# Power.net
KiCad netlist of a schematic drawn in Altium Designer
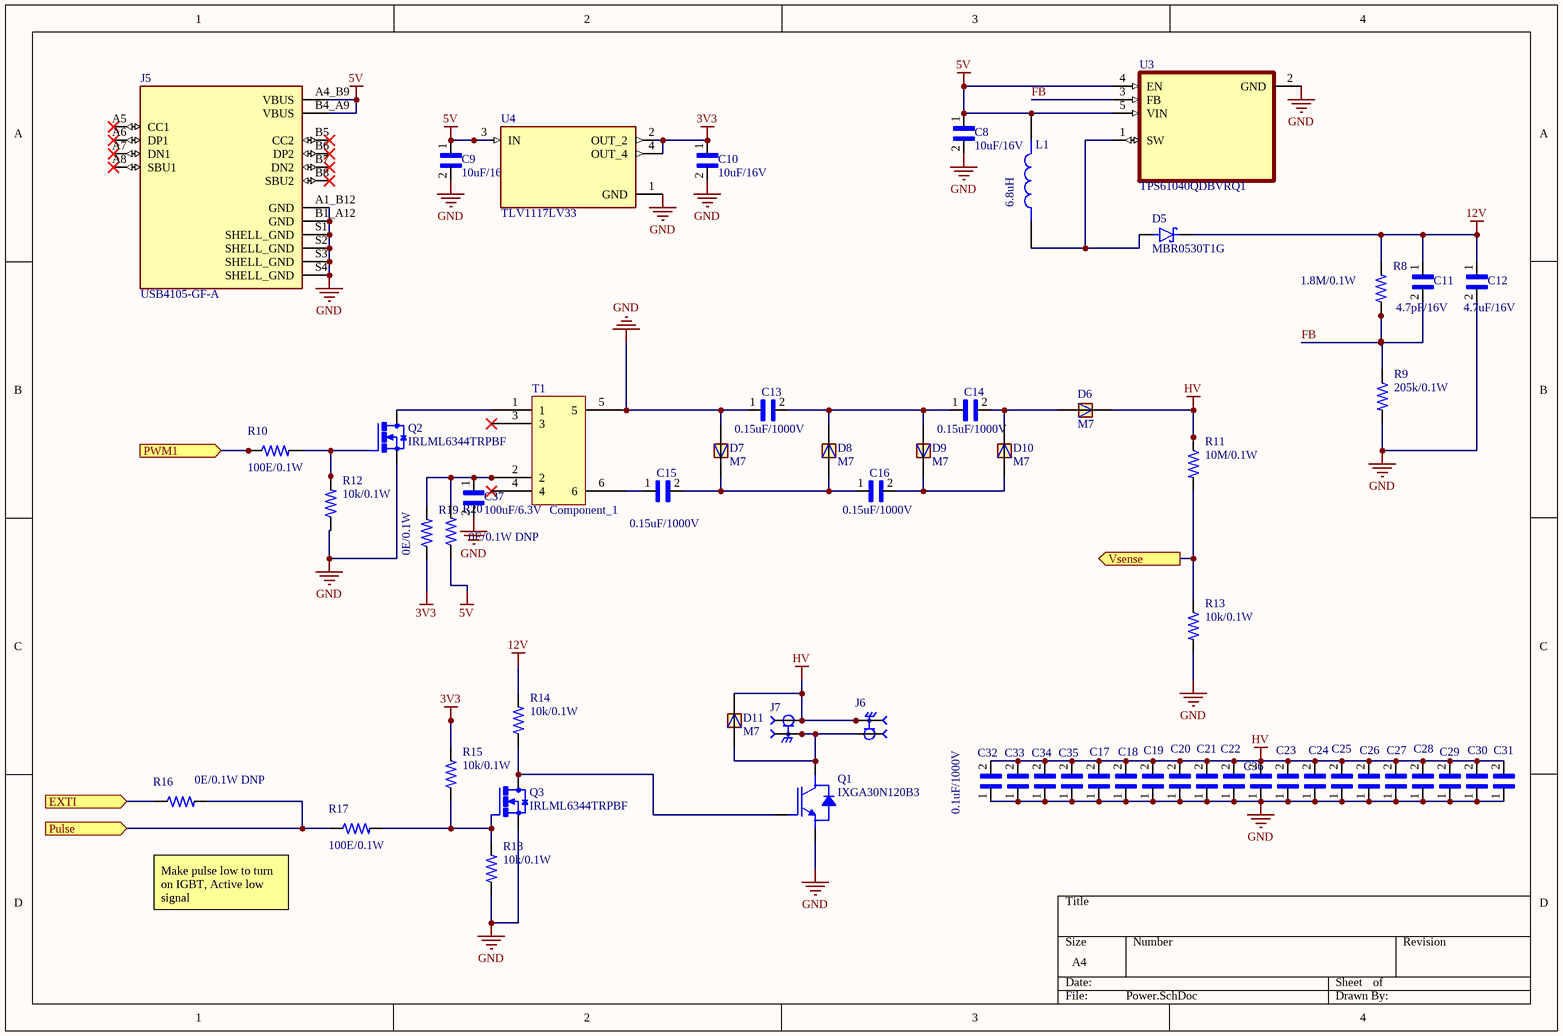
[diagram p0: Power.SchDoc]

(export (version "E")
  (design (tool "Eeschema 10.0.6"))
  (components
    (comp (ref "C8")
      (value "10uF/16V")
      (footprint "CAPC1608X90")
      (description "CAP CER 10UF 16V X5R 0603")
      (fields (field (name "MP") "CC0603MRX5R7BB106"))
      (libsource (lib "Capacitor_0603") (part "CC0603MRX5R7BB106"))
    )
    (comp (ref "C9")
      (value "10uF/16V")
      (footprint "CAPC1608X90")
      (description "CAP CER 10UF 16V X5R 0603")
      (fields (field (name "MP") "CC0603MRX5R7BB106"))
      (libsource (lib "Capacitor_0603") (part "CC0603MRX5R7BB106"))
    )
    (comp (ref "C10")
      (value "10uF/16V")
      (footprint "CAPC1608X90")
      (description "CAP CER 10UF 16V X5R 0603")
      (fields (field (name "MP") "CC0603MRX5R7BB106"))
      (libsource (lib "Capacitor_0603") (part "CC0603MRX5R7BB106"))
    )
    (comp (ref "C11")
      (value "4.7pF/16V")
      (footprint "CAPC1608X90")
      (description "CAP CER 10UF 16V X5R 0603")
      (fields (field (name "MP") "CC0603MRX5R7BB106"))
      (libsource (lib "Capacitor_0603") (part "CC0603MRX5R7BB106"))
    )
    (comp (ref "C12")
      (value "4.7uF/16V")
      (footprint "CAPC1608X90")
      (description "CAP CER 10UF 16V X5R 0603")
      (fields (field (name "MP") "CC0603MRX5R7BB106"))
      (libsource (lib "Capacitor_0603") (part "CC0603MRX5R7BB106"))
    )
    (comp (ref "C13")
      (value "0.15uF/1000V")
      (footprint "CAPC5563X218N")
      (fields (field (name "MP") "VJ2225Y104KBGAT4X"))
      (libsource (lib "Capacitor_2225") (part "VJ2225Y104KBGAT4X"))
    )
    (comp (ref "C14")
      (value "0.15uF/1000V")
      (footprint "CAPC5563X218N")
      (fields (field (name "MP") "VJ2225Y104KBGAT4X"))
      (libsource (lib "Capacitor_2225") (part "VJ2225Y104KBGAT4X"))
    )
    (comp (ref "C15")
      (value "0.15uF/1000V")
      (footprint "CAPC5563X218N")
      (fields (field (name "MP") "VJ2225Y104KBGAT4X"))
      (libsource (lib "Capacitor_2225") (part "VJ2225Y104KBGAT4X"))
    )
    (comp (ref "C16")
      (value "0.15uF/1000V")
      (footprint "CAPC5563X218N")
      (fields (field (name "MP") "VJ2225Y104KBGAT4X"))
      (libsource (lib "Capacitor_2225") (part "VJ2225Y104KBGAT4X"))
    )
    (comp (ref "C17")
      (value "0.1uF/1000V")
      (footprint "CAPC4632X221N")
      (description "1812")
      (fields (field (name "MP") "1812CC104KAZ1A") (field (name "MF") "AVX"))
      (libsource (lib "Cap_1812") (part "1812CC104KAZ1A"))
    )
    (comp (ref "C18")
      (value "0.1uF/1000V")
      (footprint "CAPC4632X221N")
      (description "1812")
      (fields (field (name "MP") "1812CC104KAZ1A") (field (name "MF") "AVX"))
      (libsource (lib "Cap_1812") (part "1812CC104KAZ1A"))
    )
    (comp (ref "C19")
      (value "0.1uF/1000V")
      (footprint "CAPC4632X221N")
      (description "1812")
      (fields (field (name "MP") "1812CC104KAZ1A") (field (name "MF") "AVX"))
      (libsource (lib "Cap_1812") (part "1812CC104KAZ1A"))
    )
    (comp (ref "C20")
      (value "0.1uF/1000V")
      (footprint "CAPC4632X221N")
      (description "1812")
      (fields (field (name "MP") "1812CC104KAZ1A") (field (name "MF") "AVX"))
      (libsource (lib "Cap_1812") (part "1812CC104KAZ1A"))
    )
    (comp (ref "C21")
      (value "0.1uF/1000V")
      (footprint "CAPC4632X221N")
      (description "1812")
      (fields (field (name "MP") "1812CC104KAZ1A") (field (name "MF") "AVX"))
      (libsource (lib "Cap_1812") (part "1812CC104KAZ1A"))
    )
    (comp (ref "C22")
      (value "0.1uF/1000V")
      (footprint "CAPC4632X221N")
      (description "1812")
      (fields (field (name "MP") "1812CC104KAZ1A") (field (name "MF") "AVX"))
      (libsource (lib "Cap_1812") (part "1812CC104KAZ1A"))
    )
    (comp (ref "C23")
      (value "0.1uF/1000V")
      (footprint "CAPC4632X221N")
      (description "1812")
      (fields (field (name "MP") "1812CC104KAZ1A") (field (name "MF") "AVX"))
      (libsource (lib "Cap_1812") (part "1812CC104KAZ1A"))
    )
    (comp (ref "C24")
      (value "0.1uF/1000V")
      (footprint "CAPC4632X221N")
      (description "1812")
      (fields (field (name "MP") "1812CC104KAZ1A") (field (name "MF") "AVX"))
      (libsource (lib "Cap_1812") (part "1812CC104KAZ1A"))
    )
    (comp (ref "C25")
      (value "0.1uF/1000V")
      (footprint "CAPC4632X221N")
      (description "1812")
      (fields (field (name "MP") "1812CC104KAZ1A") (field (name "MF") "AVX"))
      (libsource (lib "Cap_1812") (part "1812CC104KAZ1A"))
    )
    (comp (ref "C26")
      (value "0.1uF/1000V")
      (footprint "CAPC4632X221N")
      (description "1812")
      (fields (field (name "MP") "1812CC104KAZ1A") (field (name "MF") "AVX"))
      (libsource (lib "Cap_1812") (part "1812CC104KAZ1A"))
    )
    (comp (ref "C27")
      (value "0.1uF/1000V")
      (footprint "CAPC4632X221N")
      (description "1812")
      (fields (field (name "MP") "1812CC104KAZ1A") (field (name "MF") "AVX"))
      (libsource (lib "Cap_1812") (part "1812CC104KAZ1A"))
    )
    (comp (ref "C28")
      (value "0.1uF/1000V")
      (footprint "CAPC4632X221N")
      (description "1812")
      (fields (field (name "MP") "1812CC104KAZ1A") (field (name "MF") "AVX"))
      (libsource (lib "Cap_1812") (part "1812CC104KAZ1A"))
    )
    (comp (ref "C29")
      (value "0.1uF/1000V")
      (footprint "CAPC4632X221N")
      (description "1812")
      (fields (field (name "MP") "1812CC104KAZ1A") (field (name "MF") "AVX"))
      (libsource (lib "Cap_1812") (part "1812CC104KAZ1A"))
    )
    (comp (ref "C30")
      (value "0.1uF/1000V")
      (footprint "CAPC4632X221N")
      (description "1812")
      (fields (field (name "MP") "1812CC104KAZ1A") (field (name "MF") "AVX"))
      (libsource (lib "Cap_1812") (part "1812CC104KAZ1A"))
    )
    (comp (ref "C31")
      (value "0.1uF/1000V")
      (footprint "CAPC4632X221N")
      (description "1812")
      (fields (field (name "MP") "1812CC104KAZ1A") (field (name "MF") "AVX"))
      (libsource (lib "Cap_1812") (part "1812CC104KAZ1A"))
    )
    (comp (ref "C32")
      (value "0.1uF/1000V")
      (footprint "CAPC4632X221N")
      (description "1812")
      (fields (field (name "MP") "1812CC104KAZ1A") (field (name "MF") "AVX"))
      (libsource (lib "Cap_1812") (part "1812CC104KAZ1A"))
    )
    (comp (ref "C33")
      (value "0.1uF/1000V")
      (footprint "CAPC4632X221N")
      (description "1812")
      (fields (field (name "MP") "1812CC104KAZ1A") (field (name "MF") "AVX"))
      (libsource (lib "Cap_1812") (part "1812CC104KAZ1A"))
    )
    (comp (ref "C34")
      (value "0.1uF/1000V")
      (footprint "CAPC4632X221N")
      (description "1812")
      (fields (field (name "MP") "1812CC104KAZ1A") (field (name "MF") "AVX"))
      (libsource (lib "Cap_1812") (part "1812CC104KAZ1A"))
    )
    (comp (ref "C35")
      (value "0.1uF/1000V")
      (footprint "CAPC4632X221N")
      (description "1812")
      (fields (field (name "MP") "1812CC104KAZ1A") (field (name "MF") "AVX"))
      (libsource (lib "Cap_1812") (part "1812CC104KAZ1A"))
    )
    (comp (ref "C36")
      (value "0.1uF/1000V")
      (footprint "CAPC4632X221N")
      (description "1812")
      (fields (field (name "MP") "1812CC104KAZ1A") (field (name "MF") "AVX"))
      (libsource (lib "Cap_1812") (part "1812CC104KAZ1A"))
    )
    (comp (ref "C37")
      (value "100uF/6.3V")
      (footprint "CAPC1608X90")
      (description "CAP CER 10UF 16V X5R 0603")
      (fields (field (name "MP") "CC0603MRX5R7BB106"))
      (libsource (lib "Capacitor_0603") (part "CC0603MRX5R7BB106"))
    )
    (comp (ref "D5")
      (value "MBR0530T1G")
      (footprint "SOD3715X145N")
      (description "SOD-123")
      (fields (field (name "MP") "BAT46W-7-F") (field (name "MF") "Diodes Inc."))
      (libsource (lib "Diode_SOD-123") (part "BAT46W-7-F"))
    )
    (comp (ref "D6")
      (value "M7")
      (footprint "DIOM505270X240")
      (description "Diode Standard 1000 V 1A Surface Mount DO-214AC (SMA)")
      (fields (field (name "MF") "Diotec Semiconductor"))
      (libsource (lib "") (part "M7_2"))
    )
    (comp (ref "D7")
      (value "M7")
      (footprint "DIOM505270X240")
      (description "Diode Standard 1000 V 1A Surface Mount DO-214AC (SMA)")
      (fields (field (name "MF") "Diotec Semiconductor"))
      (libsource (lib "") (part "M7_1"))
    )
    (comp (ref "D8")
      (value "M7")
      (footprint "DIOM505270X240")
      (description "Diode Standard 1000 V 1A Surface Mount DO-214AC (SMA)")
      (fields (field (name "MF") "Diotec Semiconductor"))
      (libsource (lib "Diode_DO-214AC-2") (part "M7"))
    )
    (comp (ref "D9")
      (value "M7")
      (footprint "DIOM505270X240")
      (description "Diode Standard 1000 V 1A Surface Mount DO-214AC (SMA)")
      (fields (field (name "MF") "Diotec Semiconductor"))
      (libsource (lib "") (part "M7_1"))
    )
    (comp (ref "D10")
      (value "M7")
      (footprint "DIOM505270X240")
      (description "Diode Standard 1000 V 1A Surface Mount DO-214AC (SMA)")
      (fields (field (name "MF") "Diotec Semiconductor"))
      (libsource (lib "Diode_DO-214AC-2") (part "M7"))
    )
    (comp (ref "D11")
      (value "M7")
      (footprint "DIOM505270X240")
      (description "Diode Standard 1000 V 1A Surface Mount DO-214AC (SMA)")
      (fields (field (name "MF") "Diotec Semiconductor"))
      (libsource (lib "Diode_DO-214AC-2") (part "M7"))
    )
    (comp (ref "J5")
      (value "USB4105-GF-A")
      (footprint "GCT_USB4105-GF-A")
      (fields (field (name "MF") "GCT"))
      (libsource (lib "USB4105-GF-A") (part "USB4105-GF-A"))
    )
    (comp (ref "J6")
      (value "SMA-J-P-X-ST-EM3")
      (footprint "SAMTEC_SMA-J-P-X-ST-EM3")
      (description "RF Connectors / Coaxial Connectors")
      (fields (field (name "MF") "Samtec"))
      (libsource (lib "SMA-J-P-X-ST-EM3") (part "SMA-J-P-X-ST-EM3"))
    )
    (comp (ref "J7")
      (value "SMA-J-P-X-ST-EM3")
      (footprint "SAMTEC_SMA-J-P-X-ST-EM3")
      (description "RF Connectors / Coaxial Connectors")
      (fields (field (name "MF") "Samtec"))
      (libsource (lib "SMA-J-P-X-ST-EM3") (part "SMA-J-P-X-ST-EM3"))
    )
    (comp (ref "L1")
      (value "6.8uH")
      (footprint "INDM3225X240N")
      (description "1210")
      (fields (field (name "DIGI-KEY_PART_NUMBER") "445-16406-2-ND") (field (name "MP") "NLCV32T-6R8M-EFR"))
      (libsource (lib "Inductor_1210") (part "NLCV32T-6R8M-EFR"))
    )
    (comp (ref "Q1")
      (value "IXGA30N120B3")
      (footprint "TO254P1524X483-3N")
      (description "TO-263-3")
      (fields (field (name "MP") "ISL9V5045S3ST"))
      (libsource (lib "IGBT_TO-263-3") (part "ISL9V5045S3ST"))
    )
    (comp (ref "Q2")
      (value "IRLML6344TRPBF")
      (footprint "SOT23")
      (description "SOT-23-3")
      (fields (field (name "MP") "MMBF170") (field (name "MF") "ON Semiconductor"))
      (libsource (lib "NMOS_SOT-23-3") (part "MMBF170"))
    )
    (comp (ref "Q3")
      (value "IRLML6344TRPBF")
      (footprint "SOT23")
      (description "SOT-23-3")
      (fields (field (name "MP") "MMBF170") (field (name "MF") "ON Semiconductor"))
      (libsource (lib "NMOS_SOT-23-3") (part "MMBF170"))
    )
    (comp (ref "R8")
      (value "1.8M/0.1W")
      (footprint "RESC1608X50N")
      (description "RES 0.27 OHM 1% 1/10W 0603")
      (fields (field (name "MF") "TE Connectivity") (field (name "TOLERANCE") "1%"))
      (libsource (lib "Resistor_0603") (part "3-1879460-5"))
    )
    (comp (ref "R9")
      (value "205k/0.1W")
      (footprint "RESC1608X50N")
      (description "RES 0.27 OHM 1% 1/10W 0603")
      (fields (field (name "MF") "TE Connectivity") (field (name "TOLERANCE") "1%"))
      (libsource (lib "Resistor_0603") (part "3-1879460-5"))
    )
    (comp (ref "R10")
      (value "100E/0.1W")
      (footprint "RESC1608X50N")
      (description "RES 0.27 OHM 1% 1/10W 0603")
      (fields (field (name "MF") "TE Connectivity") (field (name "TOLERANCE") "1%"))
      (libsource (lib "Resistor_0603") (part "3-1879460-5"))
    )
    (comp (ref "R11")
      (value "10M/0.1W")
      (footprint "RESC1608X50N")
      (description "RES 0.27 OHM 1% 1/10W 0603")
      (fields (field (name "MF") "TE Connectivity") (field (name "TOLERANCE") "1%"))
      (libsource (lib "Resistor_0603") (part "3-1879460-5"))
    )
    (comp (ref "R12")
      (value "10k/0.1W")
      (footprint "RESC1608X50N")
      (description "RES 0.27 OHM 1% 1/10W 0603")
      (fields (field (name "MF") "TE Connectivity") (field (name "TOLERANCE") "1%"))
      (libsource (lib "Resistor_0603") (part "3-1879460-5"))
    )
    (comp (ref "R13")
      (value "10k/0.1W")
      (footprint "RESC1608X50N")
      (description "RES 0.27 OHM 1% 1/10W 0603")
      (fields (field (name "MF") "TE Connectivity") (field (name "TOLERANCE") "1%"))
      (libsource (lib "Resistor_0603") (part "3-1879460-5"))
    )
    (comp (ref "R14")
      (value "10k/0.1W")
      (footprint "RESC1608X50N")
      (description "RES 0.27 OHM 1% 1/10W 0603")
      (fields (field (name "MF") "TE Connectivity") (field (name "TOLERANCE") "1%"))
      (libsource (lib "Resistor_0603") (part "3-1879460-5"))
    )
    (comp (ref "R15")
      (value "10k/0.1W")
      (footprint "RESC1608X50N")
      (description "RES 0.27 OHM 1% 1/10W 0603")
      (fields (field (name "MF") "TE Connectivity") (field (name "TOLERANCE") "1%"))
      (libsource (lib "Resistor_0603") (part "3-1879460-5"))
    )
    (comp (ref "R16")
      (value "0E/0.1W DNP")
      (footprint "RESC1608X50N")
      (description "RES 0.27 OHM 1% 1/10W 0603")
      (fields (field (name "MF") "TE Connectivity") (field (name "TOLERANCE") "1%"))
      (libsource (lib "Resistor_0603") (part "3-1879460-5"))
    )
    (comp (ref "R17")
      (value "100E/0.1W")
      (footprint "RESC1608X50N")
      (description "RES 0.27 OHM 1% 1/10W 0603")
      (fields (field (name "MF") "TE Connectivity") (field (name "TOLERANCE") "1%"))
      (libsource (lib "Resistor_0603") (part "3-1879460-5"))
    )
    (comp (ref "R18")
      (value "10k/0.1W")
      (footprint "RESC1608X50N")
      (description "RES 0.27 OHM 1% 1/10W 0603")
      (fields (field (name "MF") "TE Connectivity") (field (name "TOLERANCE") "1%"))
      (libsource (lib "Resistor_0603") (part "3-1879460-5"))
    )
    (comp (ref "R19")
      (value "0E/0.1W")
      (footprint "RESC1608X50N")
      (description "RES 0.27 OHM 1% 1/10W 0603")
      (fields (field (name "MF") "TE Connectivity") (field (name "TOLERANCE") "1%"))
      (libsource (lib "Resistor_0603") (part "3-1879460-5"))
    )
    (comp (ref "R20")
      (value "0E/0.1W DNP")
      (footprint "RESC1608X50N")
      (description "RES 0.27 OHM 1% 1/10W 0603")
      (fields (field (name "MF") "TE Connectivity") (field (name "TOLERANCE") "1%"))
      (libsource (lib "Resistor_0603") (part "3-1879460-5"))
    )
    (comp (ref "T1")
      (value "Component_1")
      (footprint "PCBComponent_1")
      (libsource (lib "SCS-200L_") (part "Component_1"))
    )
    (comp (ref "U3")
      (value "TPS61040QDBVRQ1")
      (footprint "SOT95P280X145-5N")
      (libsource (lib "TPS61040QDBVRQ1") (part "TPS61040QDBVRQ1"))
    )
    (comp (ref "U4")
      (value "TLV1117LV33")
      (footprint "VREG_TLV1117LV33DCYR")
      (description "1-A, low-dropout voltage regulator")
      (fields (field (name "MP") "TLV1117LV33DCYR") (field (name "DIGI-KEY_PART_NUMBER") "296-28778-2-ND"))
      (libsource (lib "LDO_SOT223") (part "TLV1117LV33DCYR"))
    )
  )
  (nets
    (net (code "1") (name "/EXTI") (class "Default")
      (node (ref "R16") (pin "1") (pinfunction "1_1") (pintype "passive"))
    )
    (net (code "2") (name "/FB") (class "Default")
      (node (ref "C11") (pin "2") (pinfunction "2_2") (pintype "passive"))
      (node (ref "R8") (pin "1") (pinfunction "1_1") (pintype "passive"))
      (node (ref "R9") (pin "1") (pinfunction "1_1") (pintype "passive"))
      (node (ref "U3") (pin "3") (pinfunction "FB_3") (pintype "input"))
    )
    (net (code "3") (name "/PWM1") (class "Default")
      (node (ref "R10") (pin "1") (pinfunction "1_1") (pintype "passive"))
    )
    (net (code "4") (name "/Pulse") (class "Default")
      (node (ref "R16") (pin "2") (pinfunction "2_2") (pintype "passive"))
      (node (ref "R17") (pin "1") (pinfunction "1_1") (pintype "passive"))
    )
    (net (code "5") (name "/Vsense") (class "Default")
      (node (ref "R11") (pin "2") (pinfunction "2_2") (pintype "passive"))
      (node (ref "R13") (pin "1") (pinfunction "1_1") (pintype "passive"))
    )
    (net (code "6") (name "3V3") (class "Default")
      (node (ref "C10") (pin "1") (pinfunction "1_1") (pintype "passive"))
      (node (ref "R15") (pin "2") (pinfunction "2_2") (pintype "passive"))
      (node (ref "R19") (pin "1") (pinfunction "1_1") (pintype "passive"))
      (node (ref "U4") (pin "2") (pinfunction "OUT_2_2") (pintype "output"))
      (node (ref "U4") (pin "4") (pinfunction "OUT_4_4") (pintype "output"))
    )
    (net (code "7") (name "5V") (class "Default")
      (node (ref "C8") (pin "1") (pinfunction "1_1") (pintype "passive"))
      (node (ref "C9") (pin "1") (pinfunction "1_1") (pintype "passive"))
      (node (ref "J5") (pin "A4_B9") (pinfunction "VBUS_A4_B9") (pintype "power_in"))
      (node (ref "J5") (pin "B4_A9") (pinfunction "VBUS_B4_A9") (pintype "power_in"))
      (node (ref "L1") (pin "2") (pinfunction "2_2") (pintype "passive"))
      (node (ref "R20") (pin "1") (pinfunction "1_1") (pintype "passive"))
      (node (ref "U3") (pin "4") (pinfunction "EN_4") (pintype "input"))
      (node (ref "U3") (pin "5") (pinfunction "VIN_5") (pintype "input"))
      (node (ref "U4") (pin "3") (pinfunction "IN_3") (pintype "input"))
    )
    (net (code "8") (name "12V") (class "Default")
      (node (ref "C11") (pin "1") (pinfunction "1_1") (pintype "passive"))
      (node (ref "C12") (pin "1") (pinfunction "1_1") (pintype "passive"))
      (node (ref "D5") (pin "1") (pinfunction "K_1") (pintype "passive"))
      (node (ref "R14") (pin "2") (pinfunction "2_2") (pintype "passive"))
      (node (ref "R8") (pin "2") (pinfunction "2_2") (pintype "passive"))
    )
    (net (code "9") (name "GND") (class "Default")
      (node (ref "C10") (pin "2") (pinfunction "2_2") (pintype "passive"))
      (node (ref "C12") (pin "2") (pinfunction "2_2") (pintype "passive"))
      (node (ref "C13") (pin "1") (pinfunction "1_1") (pintype "passive"))
      (node (ref "C17") (pin "1") (pinfunction "1_1") (pintype "passive"))
      (node (ref "C18") (pin "1") (pinfunction "1_1") (pintype "passive"))
      (node (ref "C19") (pin "1") (pinfunction "1_1") (pintype "passive"))
      (node (ref "C20") (pin "1") (pinfunction "1_1") (pintype "passive"))
      (node (ref "C21") (pin "1") (pinfunction "1_1") (pintype "passive"))
      (node (ref "C22") (pin "1") (pinfunction "1_1") (pintype "passive"))
      (node (ref "C23") (pin "1") (pinfunction "1_1") (pintype "passive"))
      (node (ref "C24") (pin "1") (pinfunction "1_1") (pintype "passive"))
      (node (ref "C25") (pin "1") (pinfunction "1_1") (pintype "passive"))
      (node (ref "C26") (pin "1") (pinfunction "1_1") (pintype "passive"))
      (node (ref "C27") (pin "1") (pinfunction "1_1") (pintype "passive"))
      (node (ref "C28") (pin "1") (pinfunction "1_1") (pintype "passive"))
      (node (ref "C29") (pin "1") (pinfunction "1_1") (pintype "passive"))
      (node (ref "C30") (pin "1") (pinfunction "1_1") (pintype "passive"))
      (node (ref "C31") (pin "1") (pinfunction "1_1") (pintype "passive"))
      (node (ref "C32") (pin "1") (pinfunction "1_1") (pintype "passive"))
      (node (ref "C33") (pin "1") (pinfunction "1_1") (pintype "passive"))
      (node (ref "C34") (pin "1") (pinfunction "1_1") (pintype "passive"))
      (node (ref "C35") (pin "1") (pinfunction "1_1") (pintype "passive"))
      (node (ref "C36") (pin "1") (pinfunction "1_1") (pintype "passive"))
      (node (ref "C37") (pin "2") (pinfunction "2_2") (pintype "passive"))
      (node (ref "C8") (pin "2") (pinfunction "2_2") (pintype "passive"))
      (node (ref "C9") (pin "2") (pinfunction "2_2") (pintype "passive"))
      (node (ref "D7") (pin "A") (pinfunction "A_A") (pintype "passive"))
      (node (ref "J5") (pin "A1_B12") (pinfunction "GND_A1_B12") (pintype "power_in"))
      (node (ref "J5") (pin "B1_A12") (pinfunction "GND_B1_A12") (pintype "power_in"))
      (node (ref "J5") (pin "S1") (pinfunction "SHELL_GND_S1") (pintype "power_in"))
      (node (ref "J5") (pin "S2") (pinfunction "SHELL_GND_S2") (pintype "power_in"))
      (node (ref "J5") (pin "S3") (pinfunction "SHELL_GND_S3") (pintype "power_in"))
      (node (ref "J5") (pin "S4") (pinfunction "SHELL_GND_S4") (pintype "power_in"))
      (node (ref "Q1") (pin "3") (pinfunction "E_3") (pintype "passive"))
      (node (ref "Q2") (pin "2") (pinfunction "S_2") (pintype "passive"))
      (node (ref "Q3") (pin "2") (pinfunction "S_2") (pintype "passive"))
      (node (ref "R12") (pin "1") (pinfunction "1_1") (pintype "passive"))
      (node (ref "R13") (pin "2") (pinfunction "2_2") (pintype "passive"))
      (node (ref "R18") (pin "1") (pinfunction "1_1") (pintype "passive"))
      (node (ref "R9") (pin "2") (pinfunction "2_2") (pintype "passive"))
      (node (ref "T1") (pin "5") (pinfunction "5_5") (pintype "passive"))
      (node (ref "U3") (pin "2") (pinfunction "GND_2") (pintype "power_in"))
      (node (ref "U4") (pin "1") (pinfunction "GND_1") (pintype "power_in"))
    )
    (net (code "10") (name "HV") (class "Default")
      (node (ref "C17") (pin "2") (pinfunction "2_2") (pintype "passive"))
      (node (ref "C18") (pin "2") (pinfunction "2_2") (pintype "passive"))
      (node (ref "C19") (pin "2") (pinfunction "2_2") (pintype "passive"))
      (node (ref "C20") (pin "2") (pinfunction "2_2") (pintype "passive"))
      (node (ref "C21") (pin "2") (pinfunction "2_2") (pintype "passive"))
      (node (ref "C22") (pin "2") (pinfunction "2_2") (pintype "passive"))
      (node (ref "C23") (pin "2") (pinfunction "2_2") (pintype "passive"))
      (node (ref "C24") (pin "2") (pinfunction "2_2") (pintype "passive"))
      (node (ref "C25") (pin "2") (pinfunction "2_2") (pintype "passive"))
      (node (ref "C26") (pin "2") (pinfunction "2_2") (pintype "passive"))
      (node (ref "C27") (pin "2") (pinfunction "2_2") (pintype "passive"))
      (node (ref "C28") (pin "2") (pinfunction "2_2") (pintype "passive"))
      (node (ref "C29") (pin "2") (pinfunction "2_2") (pintype "passive"))
      (node (ref "C30") (pin "2") (pinfunction "2_2") (pintype "passive"))
      (node (ref "C31") (pin "2") (pinfunction "2_2") (pintype "passive"))
      (node (ref "C32") (pin "2") (pinfunction "2_2") (pintype "passive"))
      (node (ref "C33") (pin "2") (pinfunction "2_2") (pintype "passive"))
      (node (ref "C34") (pin "2") (pinfunction "2_2") (pintype "passive"))
      (node (ref "C35") (pin "2") (pinfunction "2_2") (pintype "passive"))
      (node (ref "C36") (pin "2") (pinfunction "2_2") (pintype "passive"))
      (node (ref "D11") (pin "C") (pinfunction "C_C") (pintype "passive"))
      (node (ref "D6") (pin "C") (pinfunction "C_C") (pintype "passive"))
      (node (ref "J6") (pin "2") (pinfunction "2_2") (pintype "passive"))
      (node (ref "J6") (pin "3") (pinfunction "2_3") (pintype "passive"))
      (node (ref "J7") (pin "1") (pinfunction "1_1") (pintype "passive"))
      (node (ref "R11") (pin "1") (pinfunction "1_1") (pintype "passive"))
    )
    (net (code "11") (name "Net-(C13-Pad2)") (class "Default")
      (node (ref "C13") (pin "2") (pinfunction "2_2") (pintype "passive"))
      (node (ref "C14") (pin "1") (pinfunction "1_1") (pintype "passive"))
      (node (ref "D8") (pin "C") (pinfunction "C_C") (pintype "passive"))
      (node (ref "D9") (pin "A") (pinfunction "A_A") (pintype "passive"))
    )
    (net (code "12") (name "Net-(C14-Pad2)") (class "Default")
      (node (ref "C14") (pin "2") (pinfunction "2_2") (pintype "passive"))
      (node (ref "D10") (pin "C") (pinfunction "C_C") (pintype "passive"))
      (node (ref "D6") (pin "A") (pinfunction "A_A") (pintype "passive"))
    )
    (net (code "13") (name "Net-(C15-Pad1)") (class "Default")
      (node (ref "C15") (pin "1") (pinfunction "1_1") (pintype "passive"))
      (node (ref "T1") (pin "6") (pinfunction "6_6") (pintype "passive"))
    )
    (net (code "14") (name "Net-(C15-Pad2)") (class "Default")
      (node (ref "C15") (pin "2") (pinfunction "2_2") (pintype "passive"))
      (node (ref "C16") (pin "1") (pinfunction "1_1") (pintype "passive"))
      (node (ref "D7") (pin "C") (pinfunction "C_C") (pintype "passive"))
      (node (ref "D8") (pin "A") (pinfunction "A_A") (pintype "passive"))
    )
    (net (code "15") (name "Net-(C16-Pad2)") (class "Default")
      (node (ref "C16") (pin "2") (pinfunction "2_2") (pintype "passive"))
      (node (ref "D10") (pin "A") (pinfunction "A_A") (pintype "passive"))
      (node (ref "D9") (pin "C") (pinfunction "C_C") (pintype "passive"))
    )
    (net (code "16") (name "Net-(C37-Pad1)") (class "Default")
      (node (ref "C37") (pin "1") (pinfunction "1_1") (pintype "passive"))
      (node (ref "R19") (pin "2") (pinfunction "2_2") (pintype "passive"))
      (node (ref "R20") (pin "2") (pinfunction "2_2") (pintype "passive"))
      (node (ref "T1") (pin "2") (pinfunction "2_2") (pintype "passive"))
    )
    (net (code "17") (name "Net-(D5-A)") (class "Default")
      (node (ref "D5") (pin "2") (pinfunction "A_2") (pintype "passive"))
      (node (ref "L1") (pin "1") (pinfunction "1_1") (pintype "passive"))
      (node (ref "U3") (pin "1") (pinfunction "SW_1") (pintype "bidirectional"))
    )
    (net (code "18") (name "Net-(Q1-C)") (class "Default")
      (node (ref "D11") (pin "A") (pinfunction "A_A") (pintype "passive"))
      (node (ref "J6") (pin "1") (pinfunction "1_1") (pintype "passive"))
      (node (ref "J7") (pin "2") (pinfunction "2_2") (pintype "passive"))
      (node (ref "J7") (pin "3") (pinfunction "2_3") (pintype "passive"))
      (node (ref "Q1") (pin "2") (pinfunction "C_2") (pintype "passive"))
    )
    (net (code "19") (name "Net-(Q1-G)") (class "Default")
      (node (ref "Q1") (pin "1") (pinfunction "G_1") (pintype "passive"))
      (node (ref "Q3") (pin "3") (pinfunction "D_3") (pintype "passive"))
      (node (ref "R14") (pin "1") (pinfunction "1_1") (pintype "passive"))
    )
    (net (code "20") (name "Net-(Q2-D)") (class "Default")
      (node (ref "Q2") (pin "3") (pinfunction "D_3") (pintype "passive"))
      (node (ref "T1") (pin "1") (pinfunction "1_1") (pintype "passive"))
    )
    (net (code "21") (name "Net-(Q2-G)") (class "Default")
      (node (ref "Q2") (pin "1") (pinfunction "G_1") (pintype "passive"))
      (node (ref "R10") (pin "2") (pinfunction "2_2") (pintype "passive"))
      (node (ref "R12") (pin "2") (pinfunction "2_2") (pintype "passive"))
    )
    (net (code "22") (name "Net-(Q3-G)") (class "Default")
      (node (ref "Q3") (pin "1") (pinfunction "G_1") (pintype "passive"))
      (node (ref "R15") (pin "1") (pinfunction "1_1") (pintype "passive"))
      (node (ref "R17") (pin "2") (pinfunction "2_2") (pintype "passive"))
      (node (ref "R18") (pin "2") (pinfunction "2_2") (pintype "passive"))
    )
    (net (code "23") (name "unconnected-(J5-CC1-PadA5)") (class "Default")
      (node (ref "J5") (pin "A5") (pinfunction "CC1_A5") (pintype "bidirectional+no_connect"))
    )
    (net (code "24") (name "unconnected-(J5-CC2-PadB5)") (class "Default")
      (node (ref "J5") (pin "B5") (pinfunction "CC2_B5") (pintype "bidirectional+no_connect"))
    )
    (net (code "25") (name "unconnected-(J5-DN1-PadA7)") (class "Default")
      (node (ref "J5") (pin "A7") (pinfunction "DN1_A7") (pintype "bidirectional+no_connect"))
    )
    (net (code "26") (name "unconnected-(J5-DN2-PadB7)") (class "Default")
      (node (ref "J5") (pin "B7") (pinfunction "DN2_B7") (pintype "bidirectional+no_connect"))
    )
    (net (code "27") (name "unconnected-(J5-DP1-PadA6)") (class "Default")
      (node (ref "J5") (pin "A6") (pinfunction "DP1_A6") (pintype "bidirectional+no_connect"))
    )
    (net (code "28") (name "unconnected-(J5-DP2-PadB6)") (class "Default")
      (node (ref "J5") (pin "B6") (pinfunction "DP2_B6") (pintype "bidirectional+no_connect"))
    )
    (net (code "29") (name "unconnected-(J5-SBU1-PadA8)") (class "Default")
      (node (ref "J5") (pin "A8") (pinfunction "SBU1_A8") (pintype "bidirectional+no_connect"))
    )
    (net (code "30") (name "unconnected-(J5-SBU2-PadB8)") (class "Default")
      (node (ref "J5") (pin "B8") (pinfunction "SBU2_B8") (pintype "bidirectional+no_connect"))
    )
    (net (code "31") (name "unconnected-(T1-Pad3)") (class "Default")
      (node (ref "T1") (pin "3") (pinfunction "3_3") (pintype "passive+no_connect"))
    )
    (net (code "32") (name "unconnected-(T1-Pad4)") (class "Default")
      (node (ref "T1") (pin "4") (pinfunction "4_4") (pintype "passive+no_connect"))
    )
  )
)
